# battery_boost_converter_TPS61200.net
KiCad netlist of a schematic drawn in EAGLE
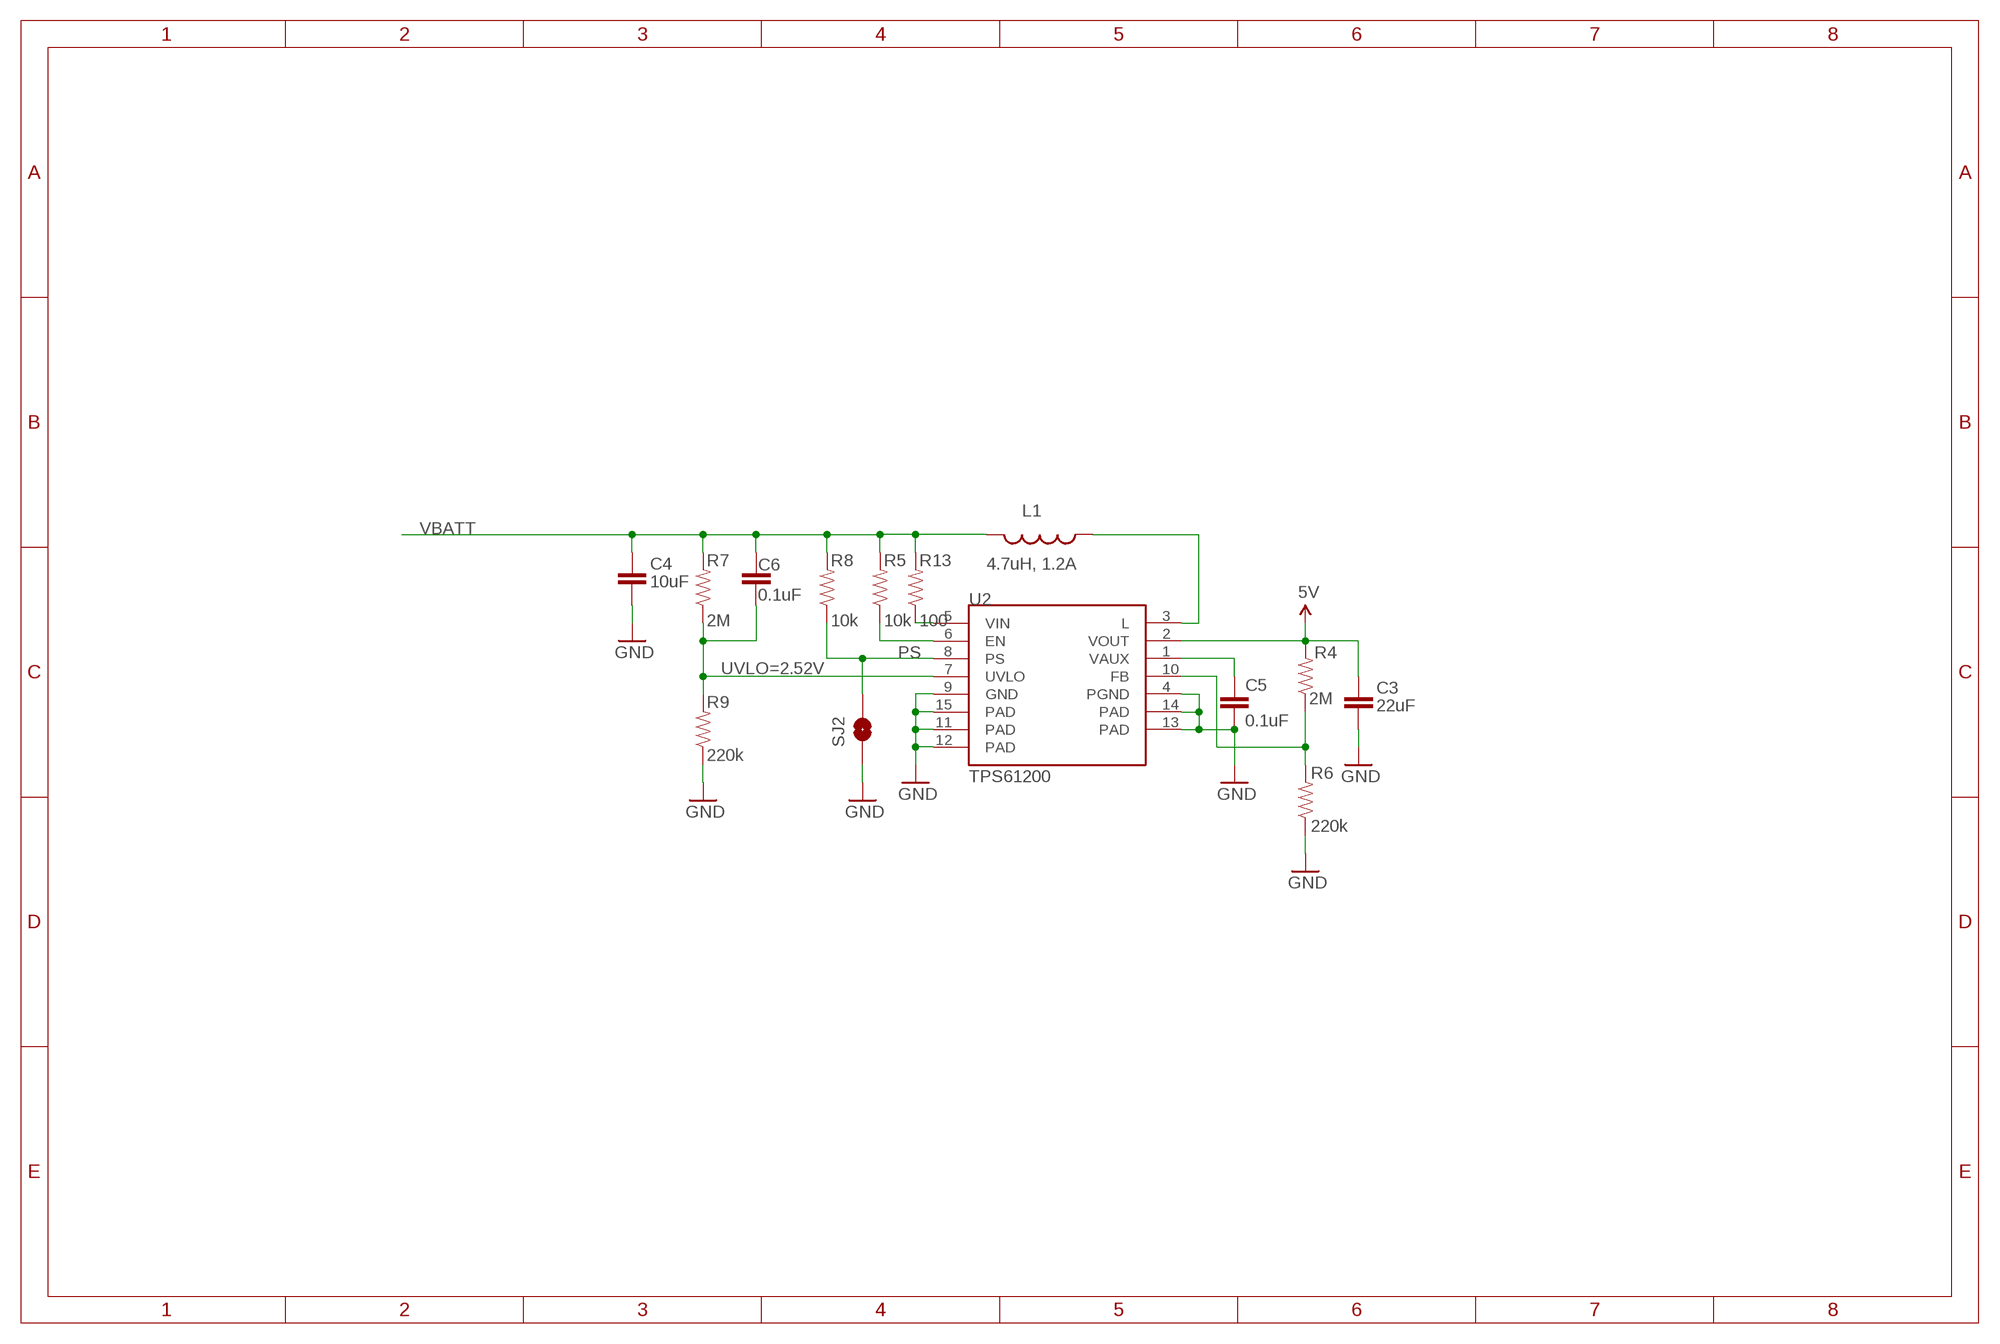
[diagram p0: schematic, sheet 1]

(export (version "E")
  (design (tool "Eeschema 10.0.6"))
  (components
    (comp (ref "C3")
      (value "22uF")
      (footprint "eagle-import:0805")
      (libsource (lib "eagle-import") (part "CAP0805"))
    )
    (comp (ref "C4")
      (value "10uF")
      (footprint "eagle-import:1206")
      (libsource (lib "eagle-import") (part "CAP1206"))
    )
    (comp (ref "C5")
      (value "0.1uF")
      (footprint "eagle-import:0402-CAP")
      (libsource (lib "eagle-import") (part "CAP0402-CAP"))
    )
    (comp (ref "C6")
      (value "0.1uF")
      (footprint "eagle-import:0402-CAP")
      (libsource (lib "eagle-import") (part "CAP0402-CAP"))
    )
    (comp (ref "L1")
      (value "4.7uH, 1.2A")
      (footprint "eagle-import:CDRH2D09")
      (libsource (lib "eagle-import") (part "INDUCTOR."))
    )
    (comp (ref "R4")
      (value "2M")
      (footprint "eagle-import:0402-RES")
      (libsource (lib "eagle-import") (part "RESISTOR0402-RES"))
    )
    (comp (ref "R5")
      (value "10k")
      (footprint "eagle-import:0402-RES")
      (libsource (lib "eagle-import") (part "RESISTOR0402-RES"))
    )
    (comp (ref "R6")
      (value "220k")
      (footprint "eagle-import:0402-RES")
      (libsource (lib "eagle-import") (part "RESISTOR0402-RES"))
    )
    (comp (ref "R7")
      (value "2M")
      (footprint "eagle-import:0402-RES")
      (libsource (lib "eagle-import") (part "RESISTOR0402-RES"))
    )
    (comp (ref "R8")
      (value "10k")
      (footprint "eagle-import:0402-RES")
      (libsource (lib "eagle-import") (part "RESISTOR0402-RES"))
    )
    (comp (ref "R9")
      (value "220k")
      (footprint "eagle-import:0402-RES")
      (libsource (lib "eagle-import") (part "RESISTOR0402-RES"))
    )
    (comp (ref "R13")
      (value "100")
      (footprint "eagle-import:0402-RES")
      (libsource (lib "eagle-import") (part "RESISTOR0402-RES"))
    )
    (comp (ref "SJ2")
      (value "PS")
      (footprint "eagle-import:SJ_2S-NO")
      (libsource (lib "eagle-import") (part "SOLDERJUMPERNO"))
    )
    (comp (ref "U2")
      (value "TPS61200")
      (footprint "eagle-import:QFN-10_PAD")
      (libsource (lib "eagle-import") (part "TPS61200"))
    )
  )
  (nets
    (net (code "1") (name "/PS") (class "Default")
      (node (ref "R8") (pin "1") (pinfunction "1_1") (pintype "passive"))
      (node (ref "SJ2") (pin "2") (pinfunction "2_2") (pintype "passive"))
      (node (ref "U2") (pin "8") (pinfunction "PS_8") (pintype "input"))
    )
    (net (code "2") (name "/VBATT") (class "Default")
      (node (ref "C4") (pin "1") (pinfunction "1_1") (pintype "passive"))
      (node (ref "C6") (pin "1") (pinfunction "1_1") (pintype "passive"))
      (node (ref "L1") (pin "P$2") (pinfunction "2_P$2") (pintype "passive"))
      (node (ref "R13") (pin "2") (pinfunction "2_2") (pintype "passive"))
      (node (ref "R5") (pin "2") (pinfunction "2_2") (pintype "passive"))
      (node (ref "R7") (pin "2") (pinfunction "2_2") (pintype "passive"))
      (node (ref "R8") (pin "2") (pinfunction "2_2") (pintype "passive"))
    )
    (net (code "3") (name "5V") (class "Default")
      (node (ref "C3") (pin "1") (pinfunction "1_1") (pintype "passive"))
      (node (ref "R4") (pin "2") (pinfunction "2_2") (pintype "passive"))
      (node (ref "U2") (pin "2") (pinfunction "VOUT_2") (pintype "passive"))
    )
    (net (code "4") (name "GND") (class "Default")
      (node (ref "C3") (pin "2") (pinfunction "2_2") (pintype "passive"))
      (node (ref "C4") (pin "2") (pinfunction "2_2") (pintype "passive"))
      (node (ref "C5") (pin "2") (pinfunction "2_2") (pintype "passive"))
      (node (ref "R6") (pin "1") (pinfunction "1_1") (pintype "passive"))
      (node (ref "R9") (pin "1") (pinfunction "1_1") (pintype "passive"))
      (node (ref "SJ2") (pin "1") (pinfunction "1_1") (pintype "passive"))
      (node (ref "U2") (pin "11") (pinfunction "PAD_11") (pintype "power_in"))
      (node (ref "U2") (pin "12") (pinfunction "PAD_12") (pintype "power_in"))
      (node (ref "U2") (pin "13") (pinfunction "PAD_13") (pintype "power_in"))
      (node (ref "U2") (pin "14") (pinfunction "PAD_14") (pintype "power_in"))
      (node (ref "U2") (pin "15") (pinfunction "PAD_15") (pintype "power_in"))
      (node (ref "U2") (pin "4") (pinfunction "PGND_4") (pintype "power_in"))
      (node (ref "U2") (pin "9") (pinfunction "GND_9") (pintype "power_in"))
    )
    (net (code "5") (name "Net-(L1-1)") (class "Default")
      (node (ref "L1") (pin "P$1") (pinfunction "1_P$1") (pintype "passive"))
      (node (ref "U2") (pin "3") (pinfunction "L_3") (pintype "passive"))
    )
    (net (code "6") (name "Net-(U2-EN)") (class "Default")
      (node (ref "R5") (pin "1") (pinfunction "1_1") (pintype "passive"))
      (node (ref "U2") (pin "6") (pinfunction "EN_6") (pintype "input"))
    )
    (net (code "7") (name "Net-(U2-FB)") (class "Default")
      (node (ref "R4") (pin "1") (pinfunction "1_1") (pintype "passive"))
      (node (ref "R6") (pin "2") (pinfunction "2_2") (pintype "passive"))
      (node (ref "U2") (pin "10") (pinfunction "FB_10") (pintype "passive"))
    )
    (net (code "8") (name "Net-(U2-UVLO)") (class "Default")
      (node (ref "C6") (pin "2") (pinfunction "2_2") (pintype "passive"))
      (node (ref "R7") (pin "1") (pinfunction "1_1") (pintype "passive"))
      (node (ref "R9") (pin "2") (pinfunction "2_2") (pintype "passive"))
      (node (ref "U2") (pin "7") (pinfunction "UVLO_7") (pintype "passive"))
    )
    (net (code "9") (name "Net-(U2-VAUX)") (class "Default")
      (node (ref "C5") (pin "1") (pinfunction "1_1") (pintype "passive"))
      (node (ref "U2") (pin "1") (pinfunction "VAUX_1") (pintype "passive"))
    )
    (net (code "10") (name "Net-(U2-VIN)") (class "Default")
      (node (ref "R13") (pin "1") (pinfunction "1_1") (pintype "passive"))
      (node (ref "U2") (pin "5") (pinfunction "VIN_5") (pintype "power_in"))
    )
  )
)
